# RS485_V3.net
KiCad netlist of a schematic drawn in EAGLE
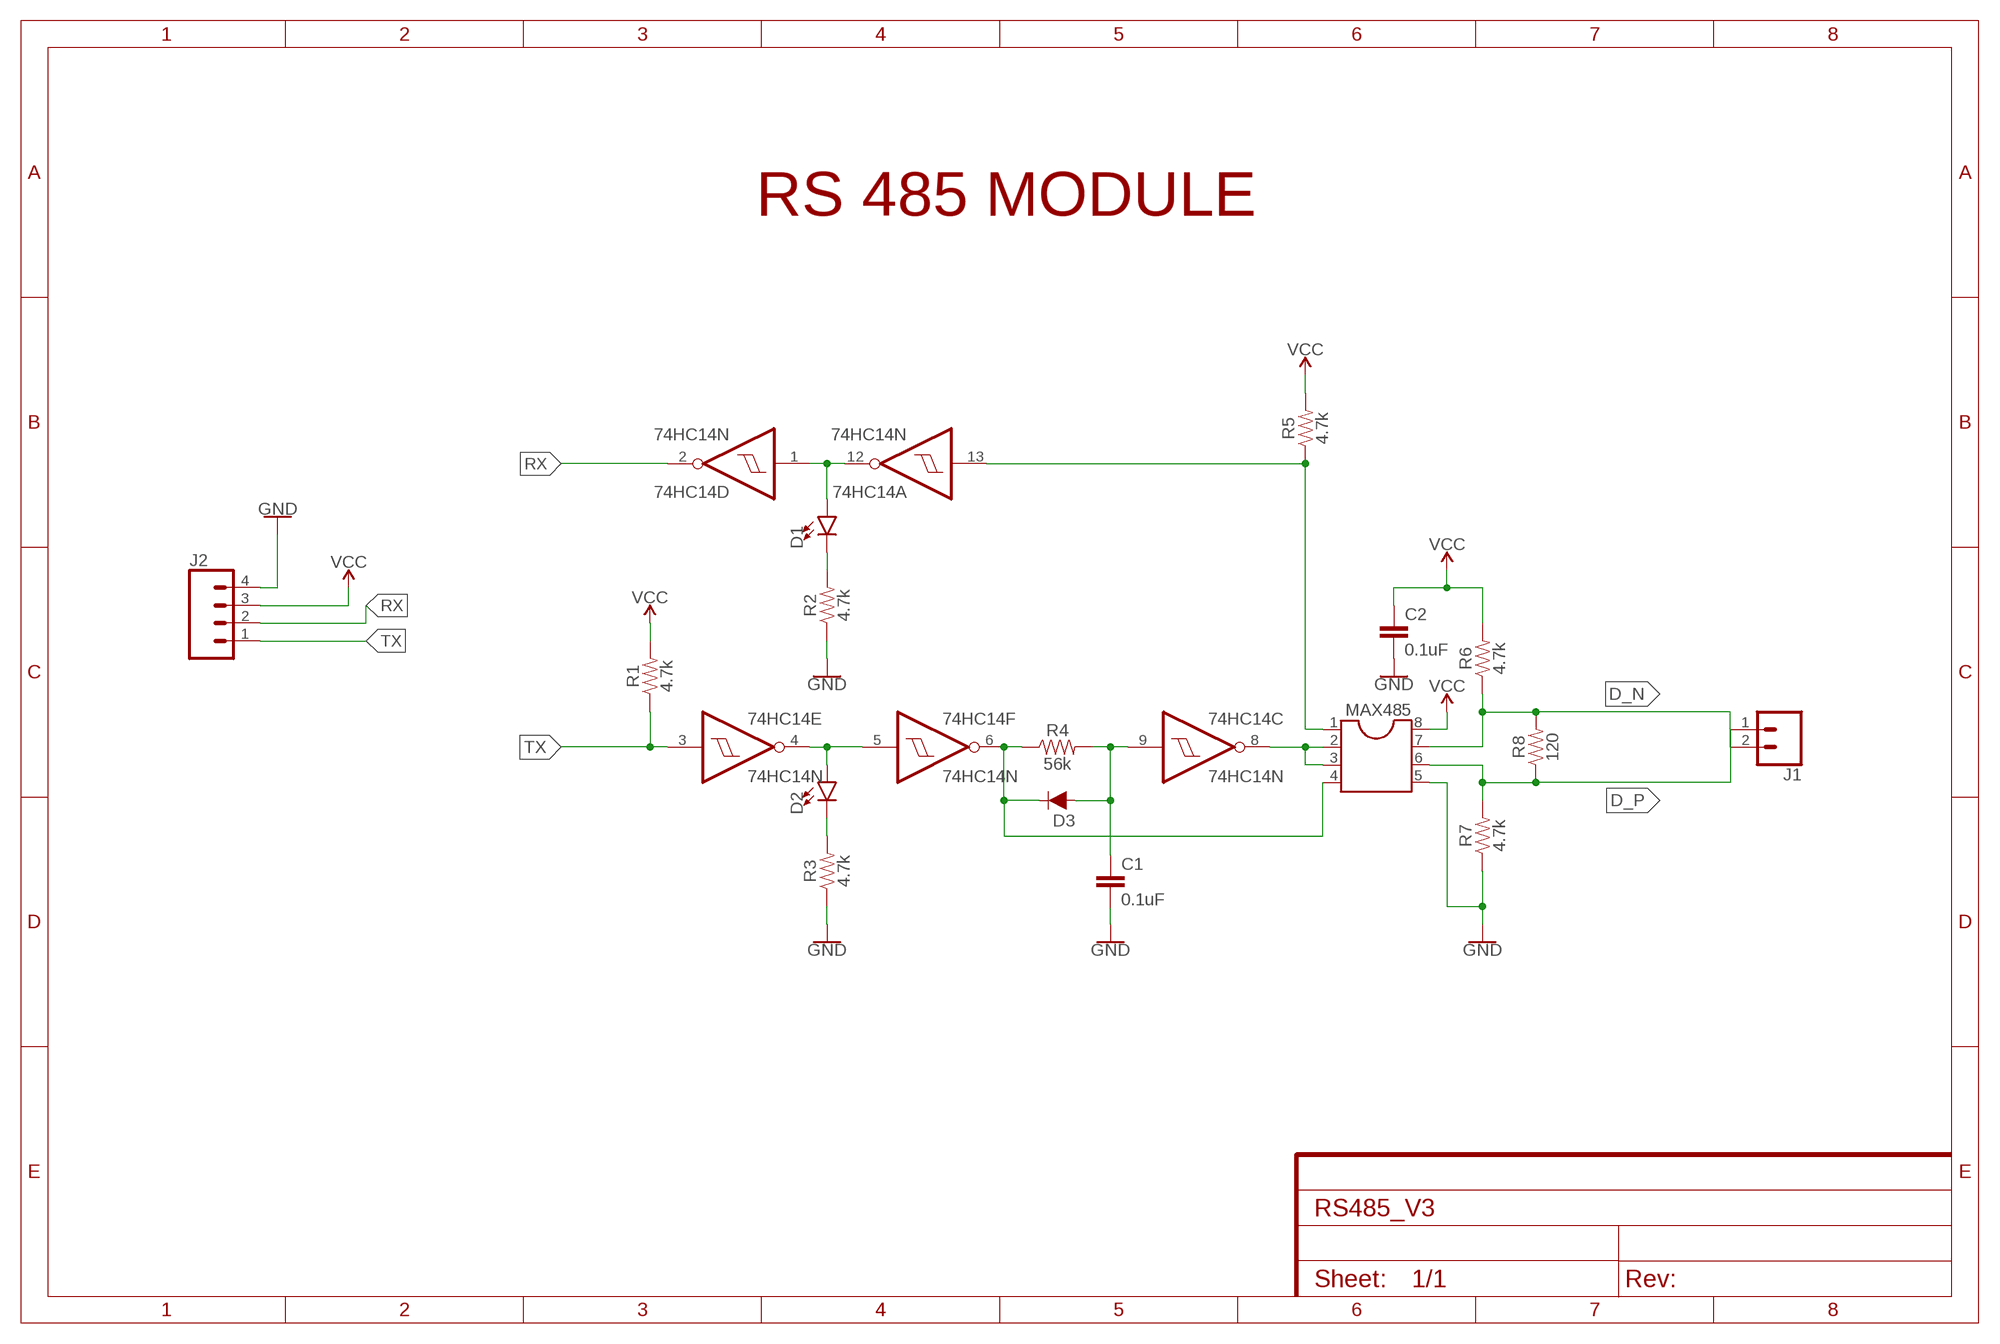
[diagram p0: schematic, sheet 1]

(export (version "E")
  (design (tool "Eeschema 10.0.6"))
  (components
    (comp (ref "74HC14")
      (value "74HC14N")
      (footprint "eagle-import:DIL14")
      (libsource (lib "eagle-import") (part "7414NHC"))
    )
    (comp (ref "C1")
      (value "0.1uF")
      (footprint "eagle-import:CAP-PTH-SMALL-KIT")
      (libsource (lib "eagle-import") (part "0.1UF-KIT-EZ-50V-20%"))
    )
    (comp (ref "C2")
      (value "0.1uF")
      (footprint "eagle-import:CAP-PTH-SMALL-KIT")
      (libsource (lib "eagle-import") (part "0.1UF-KIT-EZ-50V-20%"))
    )
    (comp (ref "D1")
      (value "LED5MM-KIT")
      (footprint "eagle-import:LED_5MM-KIT")
      (libsource (lib "eagle-import") (part "LED5MM-KIT"))
    )
    (comp (ref "D2")
      (value "LED5MM-KIT")
      (footprint "eagle-import:LED_5MM-KIT")
      (libsource (lib "eagle-import") (part "LED5MM-KIT"))
    )
    (comp (ref "D3")
      (value "200mA/100V/1V")
      (footprint "eagle-import:DIODE-1N4148")
      (libsource (lib "eagle-import") (part "DIODE-1N4148"))
    )
    (comp (ref "J1")
      (value "CONN_02POLAR")
      (footprint "eagle-import:MOLEX-1X2")
      (libsource (lib "eagle-import") (part "CONN_02POLAR"))
    )
    (comp (ref "J2")
      (value "CONN_04POLAR")
      (footprint "eagle-import:MOLEX-1X4")
      (libsource (lib "eagle-import") (part "CONN_04POLAR"))
    )
    (comp (ref "MAX485")
      (value "DIL8")
      (footprint "eagle-import:DIL08")
      (libsource (lib "eagle-import") (part "DIL8"))
    )
    (comp (ref "R1")
      (value "4.7k")
      (footprint "eagle-import:AXIAL-0.3")
      (libsource (lib "eagle-import") (part "10MOHM-HORIZ-1/4W-5%"))
    )
    (comp (ref "R2")
      (value "4.7k")
      (footprint "eagle-import:AXIAL-0.3")
      (libsource (lib "eagle-import") (part "10MOHM-HORIZ-1/4W-5%"))
    )
    (comp (ref "R3")
      (value "4.7k")
      (footprint "eagle-import:AXIAL-0.3")
      (libsource (lib "eagle-import") (part "10MOHM-HORIZ-1/4W-5%"))
    )
    (comp (ref "R4")
      (value "56k")
      (footprint "eagle-import:AXIAL-0.3")
      (libsource (lib "eagle-import") (part "10MOHM-HORIZ-1/4W-5%"))
    )
    (comp (ref "R5")
      (value "4.7k")
      (footprint "eagle-import:AXIAL-0.3")
      (libsource (lib "eagle-import") (part "10MOHM-HORIZ-1/4W-5%"))
    )
    (comp (ref "R6")
      (value "4.7k")
      (footprint "eagle-import:AXIAL-0.3")
      (libsource (lib "eagle-import") (part "10MOHM-HORIZ-1/4W-5%"))
    )
    (comp (ref "R7")
      (value "4.7k")
      (footprint "eagle-import:AXIAL-0.3")
      (libsource (lib "eagle-import") (part "10MOHM-HORIZ-1/4W-5%"))
    )
    (comp (ref "R8")
      (value "120")
      (footprint "eagle-import:AXIAL-0.3")
      (libsource (lib "eagle-import") (part "10MOHM-HORIZ-1/4W-5%"))
    )
  )
  (nets
    (net (code "1") (name "D_N") (class "Default")
      (node (ref "J1") (pin "2") (pinfunction "2_2") (pintype "passive"))
      (node (ref "MAX485") (pin "7") (pinfunction "7_7") (pintype "passive"))
      (node (ref "R6") (pin "P$1") (pinfunction "1_P$1") (pintype "passive"))
      (node (ref "R8") (pin "P$2") (pinfunction "2_P$2") (pintype "passive"))
    )
    (net (code "2") (name "D_P") (class "Default")
      (node (ref "J1") (pin "1") (pinfunction "1_1") (pintype "passive"))
      (node (ref "MAX485") (pin "6") (pinfunction "6_6") (pintype "passive"))
      (node (ref "R7") (pin "P$2") (pinfunction "2_P$2") (pintype "passive"))
      (node (ref "R8") (pin "P$1") (pinfunction "1_P$1") (pintype "passive"))
    )
    (net (code "3") (name "GND") (class "Default")
      (node (ref "C1") (pin "2") (pinfunction "2_2") (pintype "passive"))
      (node (ref "C2") (pin "2") (pinfunction "2_2") (pintype "passive"))
      (node (ref "J2") (pin "4") (pinfunction "4_4") (pintype "passive"))
      (node (ref "MAX485") (pin "5") (pinfunction "5_5") (pintype "passive"))
      (node (ref "R2") (pin "P$1") (pinfunction "1_P$1") (pintype "passive"))
      (node (ref "R3") (pin "P$1") (pinfunction "1_P$1") (pintype "passive"))
      (node (ref "R7") (pin "P$1") (pinfunction "1_P$1") (pintype "passive"))
    )
    (net (code "4") (name "Net-(74HC14A-I)") (class "Default")
      (node (ref "74HC14") (pin "13") (pinfunction "I_13") (pintype "input"))
      (node (ref "MAX485") (pin "1") (pinfunction "1_1") (pintype "passive"))
      (node (ref "R5") (pin "P$1") (pinfunction "1_P$1") (pintype "passive"))
    )
    (net (code "5") (name "Net-(74HC14A-O)") (class "Default")
      (node (ref "74HC14") (pin "1") (pinfunction "I_1") (pintype "input"))
      (node (ref "74HC14") (pin "12") (pinfunction "O_12") (pintype "output"))
      (node (ref "D1") (pin "A") (pinfunction "A_A") (pintype "passive"))
    )
    (net (code "6") (name "Net-(74HC14C-I)") (class "Default")
      (node (ref "74HC14") (pin "9") (pinfunction "I_9") (pintype "input"))
      (node (ref "C1") (pin "1") (pinfunction "1_1") (pintype "passive"))
      (node (ref "D3") (pin "A") (pinfunction "A_A") (pintype "passive"))
      (node (ref "R4") (pin "P$2") (pinfunction "2_P$2") (pintype "passive"))
    )
    (net (code "7") (name "Net-(74HC14C-O)") (class "Default")
      (node (ref "74HC14") (pin "8") (pinfunction "O_8") (pintype "output"))
      (node (ref "MAX485") (pin "2") (pinfunction "2_2") (pintype "passive"))
      (node (ref "MAX485") (pin "3") (pinfunction "3_3") (pintype "passive"))
    )
    (net (code "8") (name "Net-(74HC14E-O)") (class "Default")
      (node (ref "74HC14") (pin "4") (pinfunction "O_4") (pintype "output"))
      (node (ref "74HC14") (pin "5") (pinfunction "I_5") (pintype "input"))
      (node (ref "D2") (pin "A") (pinfunction "A_A") (pintype "passive"))
    )
    (net (code "9") (name "Net-(74HC14F-O)") (class "Default")
      (node (ref "74HC14") (pin "6") (pinfunction "O_6") (pintype "output"))
      (node (ref "D3") (pin "C") (pinfunction "C_C") (pintype "passive"))
      (node (ref "MAX485") (pin "4") (pinfunction "4_4") (pintype "passive"))
      (node (ref "R4") (pin "P$1") (pinfunction "1_P$1") (pintype "passive"))
    )
    (net (code "10") (name "Net-(D1-C)") (class "Default")
      (node (ref "D1") (pin "K") (pinfunction "C_K") (pintype "passive"))
      (node (ref "R2") (pin "P$2") (pinfunction "2_P$2") (pintype "passive"))
    )
    (net (code "11") (name "Net-(D2-C)") (class "Default")
      (node (ref "D2") (pin "K") (pinfunction "C_K") (pintype "passive"))
      (node (ref "R3") (pin "P$2") (pinfunction "2_P$2") (pintype "passive"))
    )
    (net (code "12") (name "RX") (class "Default")
      (node (ref "74HC14") (pin "2") (pinfunction "O_2") (pintype "output"))
      (node (ref "J2") (pin "2") (pinfunction "2_2") (pintype "passive"))
    )
    (net (code "13") (name "TX") (class "Default")
      (node (ref "74HC14") (pin "3") (pinfunction "I_3") (pintype "input"))
      (node (ref "J2") (pin "1") (pinfunction "1_1") (pintype "passive"))
      (node (ref "R1") (pin "P$1") (pinfunction "1_P$1") (pintype "passive"))
    )
    (net (code "14") (name "VCC") (class "Default")
      (node (ref "C2") (pin "1") (pinfunction "1_1") (pintype "passive"))
      (node (ref "J2") (pin "3") (pinfunction "3_3") (pintype "passive"))
      (node (ref "MAX485") (pin "8") (pinfunction "8_8") (pintype "passive"))
      (node (ref "R1") (pin "P$2") (pinfunction "2_P$2") (pintype "passive"))
      (node (ref "R5") (pin "P$2") (pinfunction "2_P$2") (pintype "passive"))
      (node (ref "R6") (pin "P$2") (pinfunction "2_P$2") (pintype "passive"))
    )
  )
)
